# MEMS-preamp_v05.net
KiCad netlist of a schematic drawn in EAGLE
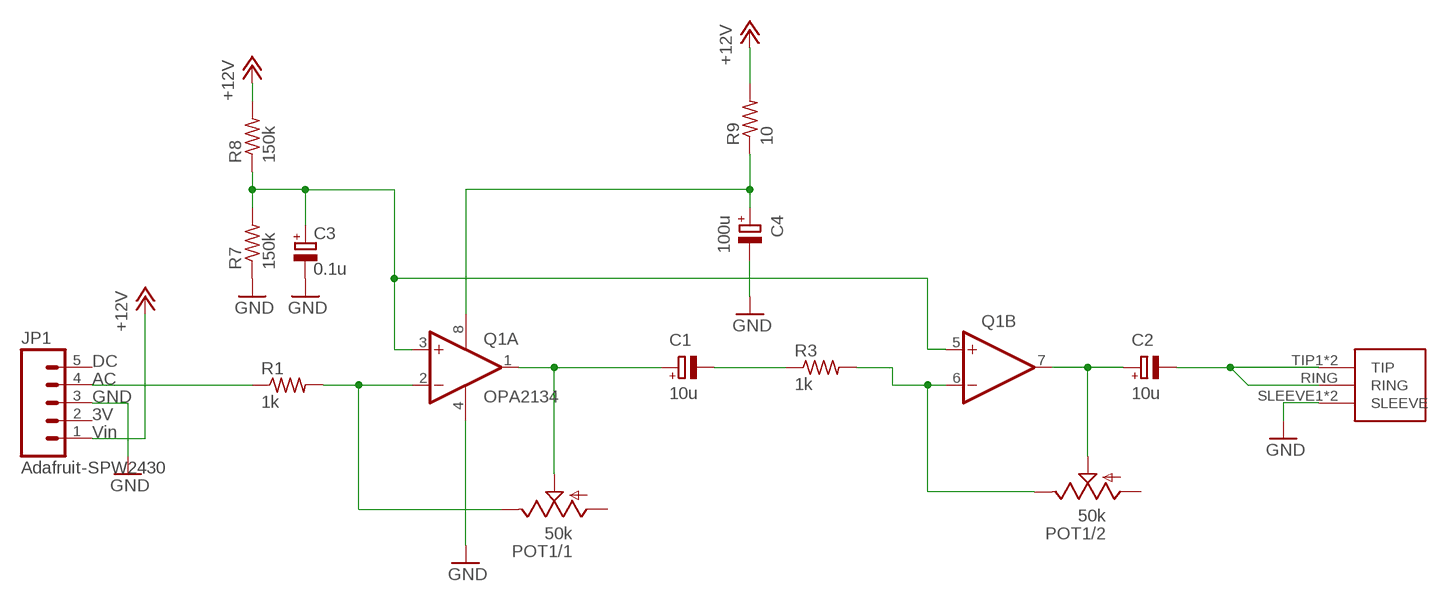
[diagram p0: schematic, sheet 1]

(export (version "E")
  (design (tool "Eeschema 10.0.6"))
  (components
    (comp (ref "C1")
      (value "10u")
      (footprint "eagle-import:E2,5-5")
      (libsource (lib "eagle-import") (part "CPOL-EUE2.5-5"))
    )
    (comp (ref "C2")
      (value "10u")
      (footprint "eagle-import:E2,5-5")
      (libsource (lib "eagle-import") (part "CPOL-EUE2.5-5"))
    )
    (comp (ref "C3")
      (value "0.1u")
      (footprint "eagle-import:E2,5-5")
      (libsource (lib "eagle-import") (part "CPOL-EUE2.5-5"))
    )
    (comp (ref "C4")
      (value "100u")
      (footprint "eagle-import:E2,5-5")
      (libsource (lib "eagle-import") (part "CPOL-EUE2.5-5"))
    )
    (comp (ref "JP1")
      (value "Adafruit-SPW2430")
      (footprint "eagle-import:1X05_LOCK")
      (fields
        (field (name "CON1") "Vin")
        (field (name "CON2") "3V")
        (field (name "CON3") "GND")
        (field (name "CON4") "AC")
        (field (name "CON5") "DC")
      )
      (libsource (lib "eagle-import") (part "M05LOCK"))
    )
    (comp (ref "POT1")
      (value "50k")
      (footprint "eagle-import:PTV112")
      (fields (field (name "MF") "STMicroelectronics") (field (name "MP") "PTV112"))
      (libsource (lib "eagle-import") (part "POT-DUAL-PTV112-4420"))
    )
    (comp (ref "Q1")
      (value "OPA2134")
      (footprint "eagle-import:DIL08")
      (fields (field (name "IC_NAME") "OPA2134"))
      (libsource (lib "eagle-import") (part "OPA2PA134"))
    )
    (comp (ref "R1")
      (value "1k")
      (footprint "eagle-import:0204_5")
      (libsource (lib "eagle-import") (part "R-US_0204/5"))
    )
    (comp (ref "R3")
      (value "1k")
      (footprint "eagle-import:0204_5")
      (libsource (lib "eagle-import") (part "R-US_0204/5"))
    )
    (comp (ref "R7")
      (value "150k")
      (footprint "eagle-import:0204_5")
      (libsource (lib "eagle-import") (part "R-US_0204/5"))
    )
    (comp (ref "R8")
      (value "150k")
      (footprint "eagle-import:0204_5")
      (libsource (lib "eagle-import") (part "R-US_0204/5"))
    )
    (comp (ref "R9")
      (value "10")
      (footprint "eagle-import:0204_5")
      (libsource (lib "eagle-import") (part "R-US_0204/5"))
    )
    (comp (ref "U$1")
      (value "1/8\"-F-STEREO-PCB")
      (footprint "eagle-import:1_8_-F-STEREO-PCB")
      (libsource (lib "eagle-import") (part "1/8{dblquote}-F-STEREO-PCB"))
    )
  )
  (nets
    (net (code "1") (name "+12V") (class "Default")
      (node (ref "JP1") (pin "1") (pinfunction "1_1") (pintype "passive"))
      (node (ref "R8") (pin "2") (pinfunction "2_2") (pintype "passive"))
      (node (ref "R9") (pin "2") (pinfunction "2_2") (pintype "passive"))
    )
    (net (code "2") (name "GND") (class "Default")
      (node (ref "C3") (pin "-") (pinfunction "-_-") (pintype "passive"))
      (node (ref "C4") (pin "-") (pinfunction "-_-") (pintype "passive"))
      (node (ref "JP1") (pin "3") (pinfunction "3_3") (pintype "passive"))
      (node (ref "Q1") (pin "4") (pinfunction "V-_4") (pintype "power_in"))
      (node (ref "R7") (pin "1") (pinfunction "1_1") (pintype "passive"))
      (node (ref "U$1") (pin "SLEEVE1") (pinfunction "SLEEVE_SLEEVE1") (pintype "bidirectional"))
      (node (ref "U$1") (pin "SLEEVE2") (pinfunction "SLEEVE_SLEEVE2") (pintype "bidirectional"))
    )
    (net (code "3") (name "Net-(C1-Pad-)") (class "Default")
      (node (ref "C1") (pin "-") (pinfunction "-_-") (pintype "passive"))
      (node (ref "R3") (pin "1") (pinfunction "1_1") (pintype "passive"))
    )
    (net (code "4") (name "Net-(C2-Pad-)") (class "Default")
      (node (ref "C2") (pin "-") (pinfunction "-_-") (pintype "passive"))
      (node (ref "U$1") (pin "RING") (pinfunction "RING_RING") (pintype "bidirectional"))
      (node (ref "U$1") (pin "TIP1") (pinfunction "TIP_TIP1") (pintype "bidirectional"))
      (node (ref "U$1") (pin "TIP2") (pinfunction "TIP_TIP2") (pintype "bidirectional"))
    )
    (net (code "5") (name "Net-(JP1-Pad4)") (class "Default")
      (node (ref "JP1") (pin "4") (pinfunction "4_4") (pintype "passive"))
      (node (ref "R1") (pin "1") (pinfunction "1_1") (pintype "passive"))
    )
    (net (code "6") (name "Net-(POT1A-E)") (class "Default")
      (node (ref "POT1") (pin "1.3") (pinfunction "E_1.3") (pintype "passive"))
      (node (ref "Q1") (pin "2") (pinfunction "-IN_2") (pintype "input"))
      (node (ref "R1") (pin "2") (pinfunction "2_2") (pintype "passive"))
    )
    (net (code "7") (name "Net-(POT1A-S)") (class "Default")
      (node (ref "C1") (pin "+") (pinfunction "+_+") (pintype "passive"))
      (node (ref "POT1") (pin "1.2") (pinfunction "S_1.2") (pintype "passive"))
      (node (ref "Q1") (pin "1") (pinfunction "OUT_1") (pintype "output"))
    )
    (net (code "8") (name "Net-(POT1B-E)") (class "Default")
      (node (ref "POT1") (pin "2.3") (pinfunction "E_2.3") (pintype "passive"))
      (node (ref "Q1") (pin "6") (pinfunction "-IN_6") (pintype "input"))
      (node (ref "R3") (pin "2") (pinfunction "2_2") (pintype "passive"))
    )
    (net (code "9") (name "Net-(POT1B-S)") (class "Default")
      (node (ref "C2") (pin "+") (pinfunction "+_+") (pintype "passive"))
      (node (ref "POT1") (pin "2.2") (pinfunction "S_2.2") (pintype "passive"))
      (node (ref "Q1") (pin "7") (pinfunction "OUT_7") (pintype "output"))
    )
    (net (code "10") (name "Net-(Q1A-+IN)") (class "Default")
      (node (ref "C3") (pin "+") (pinfunction "+_+") (pintype "passive"))
      (node (ref "Q1") (pin "3") (pinfunction "+IN_3") (pintype "input"))
      (node (ref "Q1") (pin "5") (pinfunction "+IN_5") (pintype "input"))
      (node (ref "R7") (pin "2") (pinfunction "2_2") (pintype "passive"))
      (node (ref "R8") (pin "1") (pinfunction "1_1") (pintype "passive"))
    )
    (net (code "11") (name "Net-(Q1A-V+)") (class "Default")
      (node (ref "C4") (pin "+") (pinfunction "+_+") (pintype "passive"))
      (node (ref "Q1") (pin "8") (pinfunction "V+_8") (pintype "power_in"))
      (node (ref "R9") (pin "1") (pinfunction "1_1") (pintype "passive"))
    )
    (net (code "12") (name "unconnected-(JP1-Pad2)") (class "Default")
      (node (ref "JP1") (pin "2") (pinfunction "2_2") (pintype "passive"))
    )
    (net (code "13") (name "unconnected-(JP1-Pad5)") (class "Default")
      (node (ref "JP1") (pin "5") (pinfunction "5_5") (pintype "passive"))
    )
    (net (code "14") (name "unconnected-(POT1A-A-Pad1.1)") (class "Default")
      (node (ref "POT1") (pin "1.1") (pinfunction "A_1.1") (pintype "passive"))
    )
    (net (code "15") (name "unconnected-(POT1B-A-Pad2.1)") (class "Default")
      (node (ref "POT1") (pin "2.1") (pinfunction "A_2.1") (pintype "passive"))
    )
  )
)
